# blue_pill.net
KiCad netlist of a schematic drawn in Altium Designer
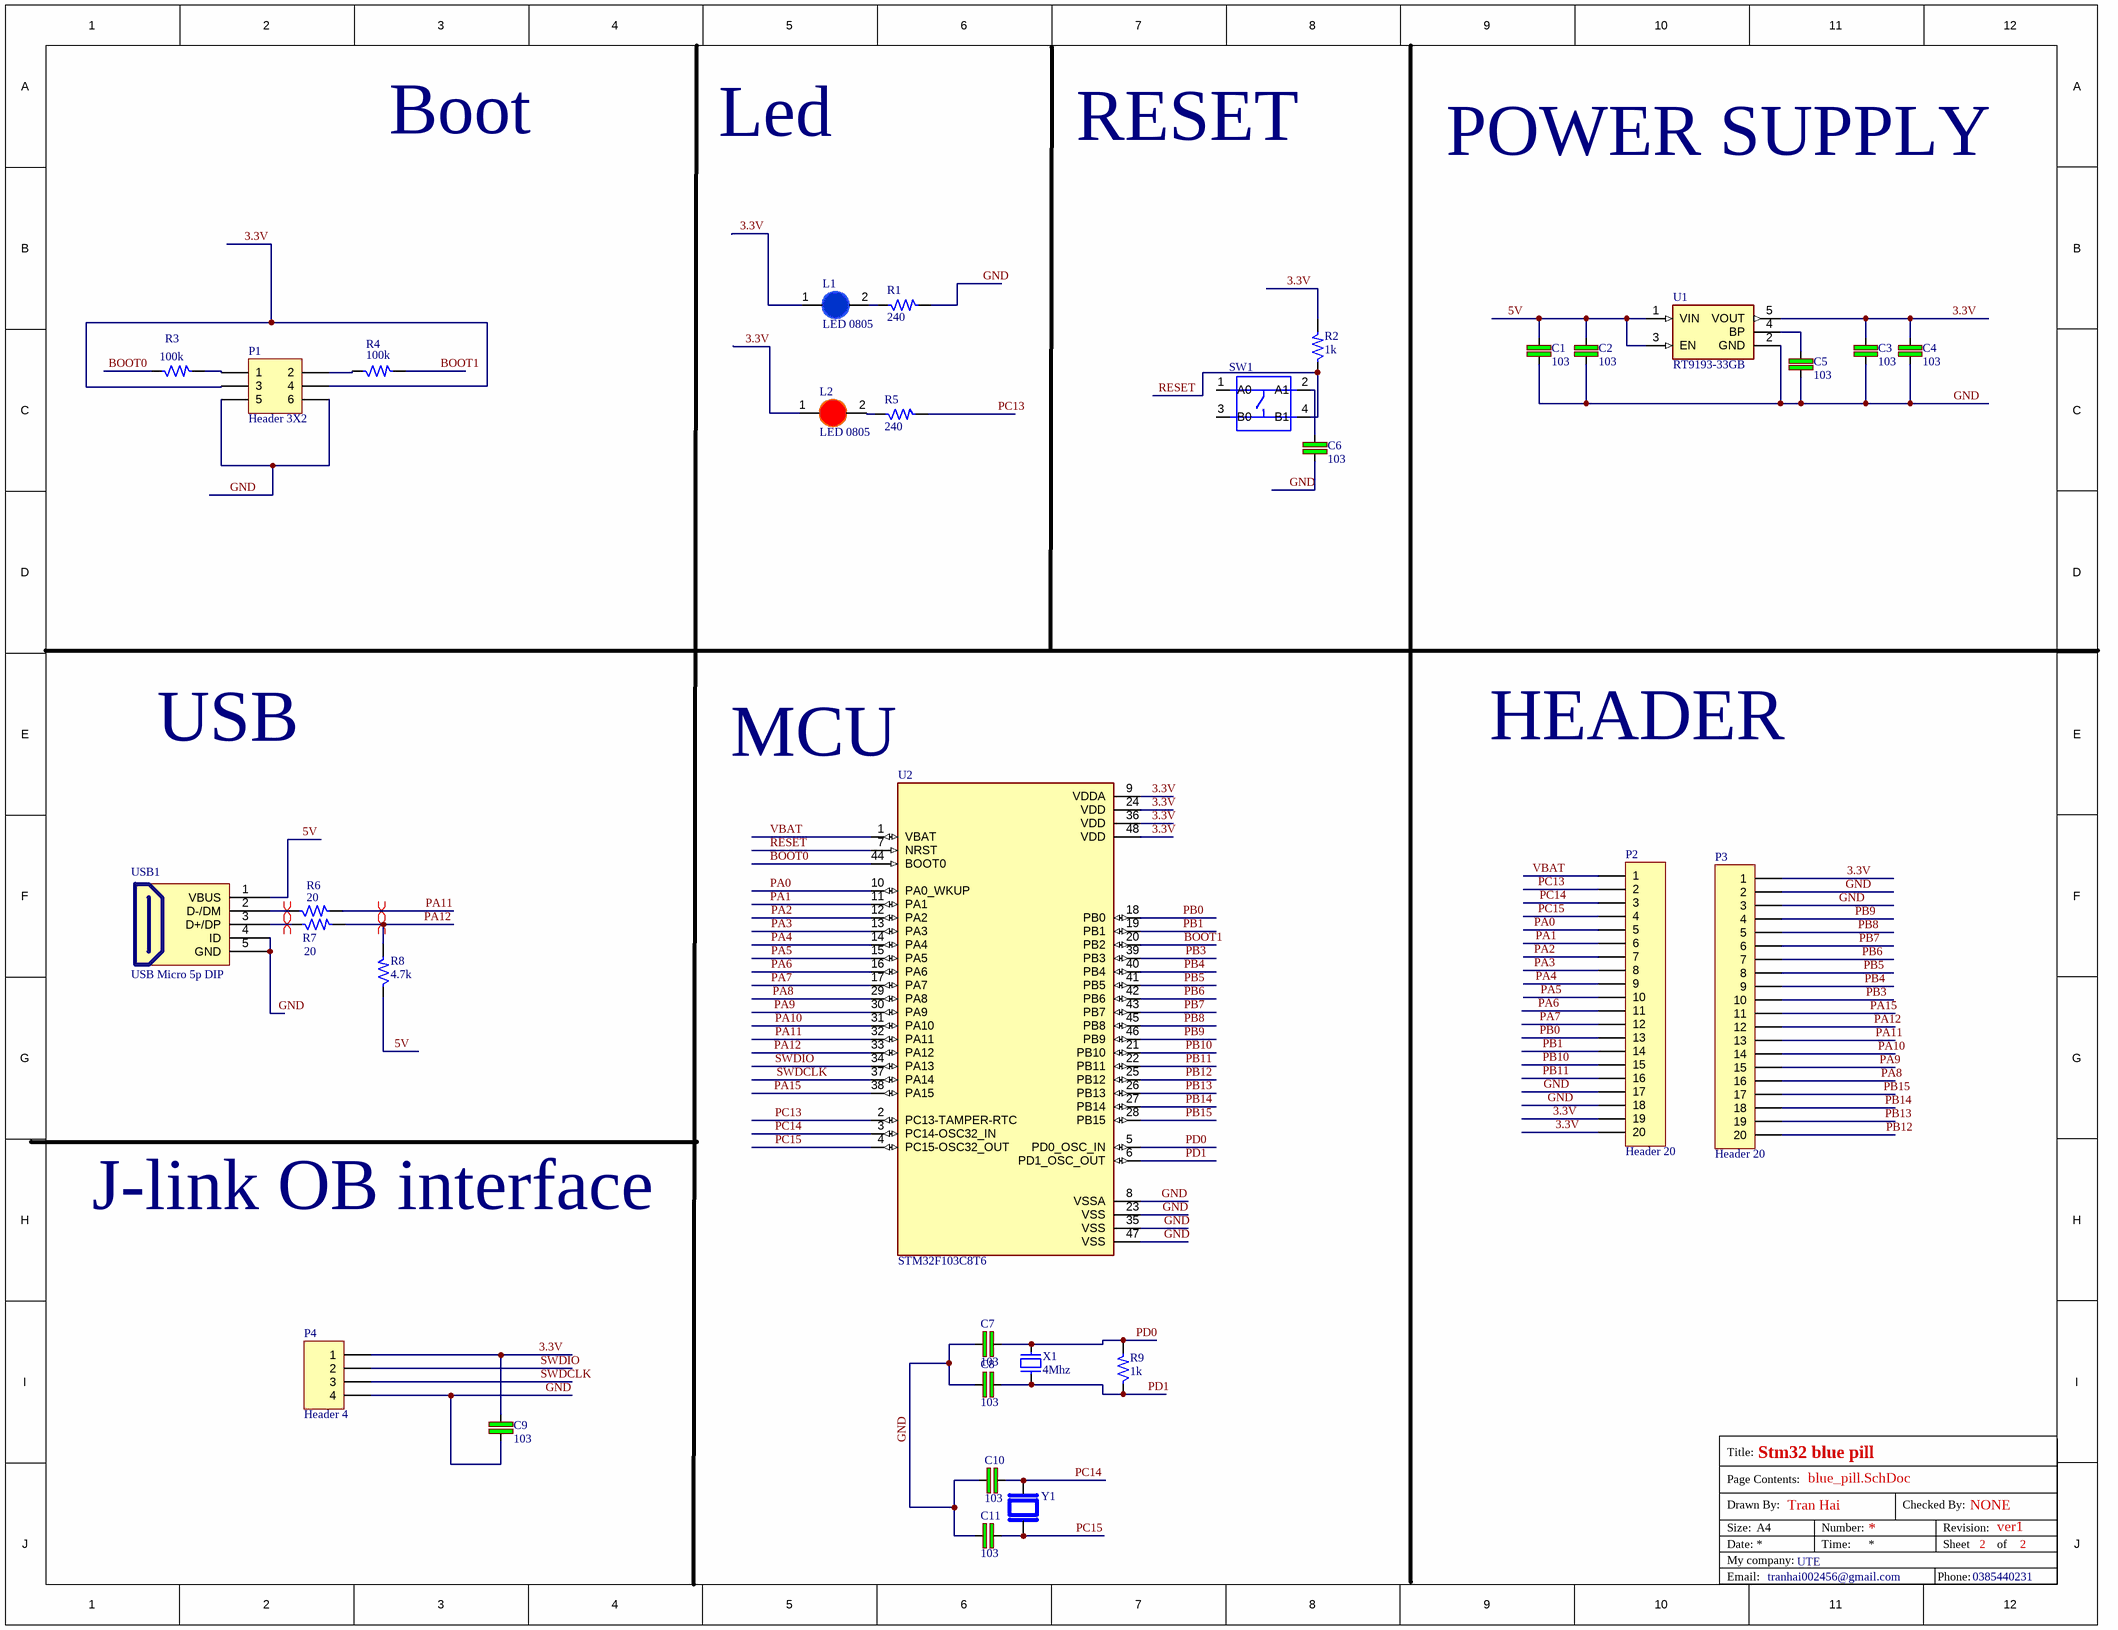
[diagram p0: blue_pill.SchDoc]

(export (version "E")
  (design (tool "Eeschema 10.0.6"))
  (components
    (comp (ref "C1")
      (value "103")
      (footprint "C-0805")
      (description "Cap SMD")
      (libsource (lib "") (part "C_1"))
    )
    (comp (ref "C2")
      (value "103")
      (footprint "C-0805")
      (description "Cap SMD")
      (libsource (lib "") (part "C_1"))
    )
    (comp (ref "C3")
      (value "103")
      (footprint "C-0805")
      (description "Cap SMD")
      (libsource (lib "") (part "C_1"))
    )
    (comp (ref "C4")
      (value "103")
      (footprint "C-0805")
      (description "Cap SMD")
      (libsource (lib "") (part "C_1"))
    )
    (comp (ref "C5")
      (value "103")
      (footprint "C-0805")
      (description "Cap SMD")
      (libsource (lib "") (part "C_1"))
    )
    (comp (ref "C6")
      (value "103")
      (footprint "C-0805")
      (description "Cap SMD")
      (libsource (lib "") (part "C_1"))
    )
    (comp (ref "C7")
      (value "103")
      (footprint "C-0805")
      (description "Cap SMD")
      (libsource (lib "Library AL") (part "C"))
    )
    (comp (ref "C8")
      (value "103")
      (footprint "C-0805")
      (description "Cap SMD")
      (libsource (lib "Library AL") (part "C"))
    )
    (comp (ref "C9")
      (value "103")
      (footprint "C-0805")
      (description "Cap SMD")
      (libsource (lib "") (part "C_1"))
    )
    (comp (ref "C10")
      (value "103")
      (footprint "C-0805")
      (description "Cap SMD")
      (libsource (lib "Library AL") (part "C"))
    )
    (comp (ref "C11")
      (value "103")
      (footprint "C-0805")
      (description "Cap SMD")
      (libsource (lib "Library AL") (part "C"))
    )
    (comp (ref "L1")
      (value "LED 0805")
      (footprint "LED-0805-Blue")
      (description "Dán")
      (libsource (lib "Altium_Lib_by_KhueNguyenCreator") (part "LED 0805 Xanh Duong"))
    )
    (comp (ref "L2")
      (value "LED 0805")
      (footprint "LED-0805-Red")
      (description "Dán")
      (libsource (lib "Altium_Lib_by_KhueNguyenCreator") (part "LED 0805 Do"))
    )
    (comp (ref "P1")
      (value "Header 3X2")
      (footprint "HDR2X3")
      (description "Header, 3-Pin, Dual row")
      (fields (field (name "PUBLISHER") "Altium Limited"))
      (libsource (lib "Library AL") (part "Header 3X2"))
    )
    (comp (ref "P2")
      (value "Header 20")
      (footprint "HDR1X20")
      (description "Header, 20-Pin")
      (fields (field (name "PUBLISHER") "Altium Limited"))
      (libsource (lib "Library AL") (part "Header 20"))
    )
    (comp (ref "P3")
      (value "Header 20")
      (footprint "HDR1X20")
      (description "Header, 20-Pin")
      (fields (field (name "PUBLISHER") "Altium Limited"))
      (libsource (lib "") (part "Header 20_1"))
    )
    (comp (ref "P4")
      (value "Header 4")
      (footprint "HDR1X4")
      (description "Header, 4-Pin")
      (fields (field (name "PUBLISHER") "Altium Limited"))
      (libsource (lib "Library AL") (part "Header 4"))
    )
    (comp (ref "R1")
      (value "240")
      (footprint "SM-1206")
      (description "Resistor 1/4W")
      (libsource (lib "Library AL") (part "R"))
    )
    (comp (ref "R2")
      (value "1k")
      (footprint "SM-1206")
      (description "Resistor 1/4W")
      (libsource (lib "Library AL") (part "R"))
    )
    (comp (ref "R3")
      (value "100k")
      (footprint "SM-1206")
      (description "Resistor 1/4W")
      (libsource (lib "Library AL") (part "R"))
    )
    (comp (ref "R4")
      (value "100k")
      (footprint "SM-1206")
      (description "Resistor 1/4W")
      (libsource (lib "Library AL") (part "R"))
    )
    (comp (ref "R5")
      (value "240")
      (footprint "SM-1206")
      (description "Resistor 1/4W")
      (libsource (lib "Library AL") (part "R"))
    )
    (comp (ref "R6")
      (value "20")
      (footprint "SM-1206")
      (description "Resistor 1/4W")
      (libsource (lib "Library AL") (part "R"))
    )
    (comp (ref "R7")
      (value "20")
      (footprint "SM-1206")
      (description "Resistor 1/4W")
      (libsource (lib "Library AL") (part "R"))
    )
    (comp (ref "R8")
      (value "4.7k")
      (footprint "SM-1206")
      (description "Resistor 1/4W")
      (libsource (lib "Library AL") (part "R"))
    )
    (comp (ref "R9")
      (value "1k")
      (footprint "SM-1206")
      (description "Resistor 1/4W")
      (libsource (lib "Library AL") (part "R"))
    )
    (comp (ref "SW1")
      (value "SMD-BUTTON(4P-5.2X5.2X1.5MM-SKQGAKE010)")
      (footprint "SW4-SMD-5.2X5.2X1.5MM")
      (description "Switch Tactile N.O. SPST Button Gull Wing 0.05A 12VDC 3.43N SMD T/R")
      (fields (field (name "MF") "ALPS") (field (name "MP") "SKQGAKE010"))
      (libsource (lib "SMD-BUTTON_4P-5.2X5.2X1.5MM-SKQGAKE010_") (part "SMD-BUTTON(4P-5.2X5.2X1.5MM-SKQGAKE010)"))
    )
    (comp (ref "U1")
      (value "RT9193-33GB")
      (footprint "SOT94P279X129-5N")
      (description "Linear Voltage Regulator IC Positive Fixed 1 Output 300mA TSOT-23-5")
      (fields (field (name "MF") "Richtek USA") (field (name "DIGI-KEY_PART_NUMBER") "1028-1014-2-ND"))
      (libsource (lib "RT9193-33GB") (part "RT9193-33GB"))
    )
    (comp (ref "U2")
      (value "STM32F103C8T6")
      (footprint "QFP50P900X900X160-48N")
      (description "ARM® Cortex®-M3 STM32F1 Microcontroller IC 32-Bit 72MHz 64KB (64K x 8) FLASH 48-LQFP (7x7)")
      (fields (field (name "MF") "STMicroelectronics"))
      (libsource (lib "STM32F103C8T6") (part "STM32F103C8T6"))
    )
    (comp (ref "USB1")
      (value "USB Micro 5p DIP")
      (footprint "USB Micro 5p DIP")
      (description "USB Type B")
      (libsource (lib "Altium_Lib_by_KhueNguyenCreator") (part "USB Micro 5p DIP"))
    )
    (comp (ref "X1")
      (value "4Mhz")
      (footprint "XT2")
      (description "Crystal For all Crystal 2pin.")
      (libsource (lib "syhaunguyen") (part "XT2"))
    )
    (comp (ref "Y1")
      (value "ABS07-32.768KHZ-T")
      (footprint "XTAL_ABS07-32.768KHZ-T")
      (description "32.768 kHz Â±20ppm Crystal 12.5pF 70 kOhms 2-SMD, No Lead")
      (fields (field (name "MF") "Abracon"))
      (libsource (lib "ABS07-32.768KHZ-T") (part "ABS07-32.768KHZ-T"))
    )
  )
  (nets
    (net (code "1") (name "/3.3V") (class "Default")
      (node (ref "C3") (pin "2") (pinfunction "2_2") (pintype "passive"))
      (node (ref "C4") (pin "2") (pinfunction "2_2") (pintype "passive"))
      (node (ref "C9") (pin "2") (pinfunction "2_2") (pintype "passive"))
      (node (ref "L1") (pin "1") (pinfunction "A_1") (pintype "passive"))
      (node (ref "L2") (pin "1") (pinfunction "A_1") (pintype "passive"))
      (node (ref "P1") (pin "3") (pinfunction "3_3") (pintype "passive"))
      (node (ref "P1") (pin "4") (pinfunction "4_4") (pintype "passive"))
      (node (ref "P2") (pin "19") (pinfunction "19_19") (pintype "passive"))
      (node (ref "P2") (pin "20") (pinfunction "20_20") (pintype "passive"))
      (node (ref "P3") (pin "1") (pinfunction "1_1") (pintype "passive"))
      (node (ref "P4") (pin "1") (pinfunction "1_1") (pintype "passive"))
      (node (ref "R2") (pin "2") (pinfunction "2_2") (pintype "passive"))
      (node (ref "U1") (pin "5") (pinfunction "VOUT_5") (pintype "output"))
      (node (ref "U2") (pin "24") (pinfunction "VDD_24") (pintype "power_in"))
      (node (ref "U2") (pin "36") (pinfunction "VDD_36") (pintype "power_in"))
      (node (ref "U2") (pin "48") (pinfunction "VDD_48") (pintype "power_in"))
      (node (ref "U2") (pin "9") (pinfunction "VDDA_9") (pintype "power_in"))
    )
    (net (code "2") (name "/5V") (class "Default")
      (node (ref "C1") (pin "2") (pinfunction "2_2") (pintype "passive"))
      (node (ref "C2") (pin "2") (pinfunction "2_2") (pintype "passive"))
      (node (ref "R8") (pin "1") (pinfunction "1_1") (pintype "passive"))
      (node (ref "U1") (pin "1") (pinfunction "VIN_1") (pintype "input"))
      (node (ref "U1") (pin "3") (pinfunction "EN_3") (pintype "input"))
      (node (ref "USB1") (pin "1") (pinfunction "VBUS_1") (pintype "passive"))
    )
    (net (code "3") (name "/BOOT0") (class "Default")
      (node (ref "R3") (pin "1") (pinfunction "1_1") (pintype "passive"))
      (node (ref "U2") (pin "44") (pinfunction "BOOT0_44") (pintype "input"))
    )
    (net (code "4") (name "/BOOT1") (class "Default")
      (node (ref "R4") (pin "2") (pinfunction "2_2") (pintype "passive"))
      (node (ref "U2") (pin "20") (pinfunction "PB2_20") (pintype "bidirectional"))
    )
    (net (code "5") (name "/GND") (class "Default")
      (node (ref "C1") (pin "1") (pinfunction "1_1") (pintype "passive"))
      (node (ref "C10") (pin "1") (pinfunction "1_1") (pintype "passive"))
      (node (ref "C11") (pin "1") (pinfunction "1_1") (pintype "passive"))
      (node (ref "C2") (pin "1") (pinfunction "1_1") (pintype "passive"))
      (node (ref "C3") (pin "1") (pinfunction "1_1") (pintype "passive"))
      (node (ref "C4") (pin "1") (pinfunction "1_1") (pintype "passive"))
      (node (ref "C5") (pin "1") (pinfunction "1_1") (pintype "passive"))
      (node (ref "C6") (pin "1") (pinfunction "1_1") (pintype "passive"))
      (node (ref "C7") (pin "1") (pinfunction "1_1") (pintype "passive"))
      (node (ref "C8") (pin "1") (pinfunction "1_1") (pintype "passive"))
      (node (ref "C9") (pin "1") (pinfunction "1_1") (pintype "passive"))
      (node (ref "P1") (pin "5") (pinfunction "5_5") (pintype "passive"))
      (node (ref "P1") (pin "6") (pinfunction "6_6") (pintype "passive"))
      (node (ref "P2") (pin "17") (pinfunction "17_17") (pintype "passive"))
      (node (ref "P2") (pin "18") (pinfunction "18_18") (pintype "passive"))
      (node (ref "P3") (pin "2") (pinfunction "2_2") (pintype "passive"))
      (node (ref "P3") (pin "3") (pinfunction "3_3") (pintype "passive"))
      (node (ref "P4") (pin "4") (pinfunction "4_4") (pintype "passive"))
      (node (ref "R1") (pin "2") (pinfunction "2_2") (pintype "passive"))
      (node (ref "U1") (pin "2") (pinfunction "GND_2") (pintype "power_in"))
      (node (ref "U2") (pin "23") (pinfunction "VSS_23") (pintype "power_in"))
      (node (ref "U2") (pin "35") (pinfunction "VSS_35") (pintype "power_in"))
      (node (ref "U2") (pin "47") (pinfunction "VSS_47") (pintype "power_in"))
      (node (ref "U2") (pin "8") (pinfunction "VSSA_8") (pintype "power_in"))
      (node (ref "USB1") (pin "4") (pinfunction "ID_4") (pintype "passive"))
      (node (ref "USB1") (pin "5") (pinfunction "GND_5") (pintype "passive"))
    )
    (net (code "6") (name "/PA0") (class "Default")
      (node (ref "P2") (pin "5") (pinfunction "5_5") (pintype "passive"))
      (node (ref "U2") (pin "10") (pinfunction "PA0_WKUP_10") (pintype "bidirectional"))
    )
    (net (code "7") (name "/PA1") (class "Default")
      (node (ref "P2") (pin "6") (pinfunction "6_6") (pintype "passive"))
      (node (ref "U2") (pin "11") (pinfunction "PA1_11") (pintype "bidirectional"))
    )
    (net (code "8") (name "/PA2") (class "Default")
      (node (ref "P2") (pin "7") (pinfunction "7_7") (pintype "passive"))
      (node (ref "U2") (pin "12") (pinfunction "PA2_12") (pintype "bidirectional"))
    )
    (net (code "9") (name "/PA3") (class "Default")
      (node (ref "P2") (pin "8") (pinfunction "8_8") (pintype "passive"))
      (node (ref "U2") (pin "13") (pinfunction "PA3_13") (pintype "bidirectional"))
    )
    (net (code "10") (name "/PA4") (class "Default")
      (node (ref "P2") (pin "9") (pinfunction "9_9") (pintype "passive"))
      (node (ref "U2") (pin "14") (pinfunction "PA4_14") (pintype "bidirectional"))
    )
    (net (code "11") (name "/PA5") (class "Default")
      (node (ref "P2") (pin "10") (pinfunction "10_10") (pintype "passive"))
      (node (ref "U2") (pin "15") (pinfunction "PA5_15") (pintype "bidirectional"))
    )
    (net (code "12") (name "/PA6") (class "Default")
      (node (ref "P2") (pin "11") (pinfunction "11_11") (pintype "passive"))
      (node (ref "U2") (pin "16") (pinfunction "PA6_16") (pintype "bidirectional"))
    )
    (net (code "13") (name "/PA7") (class "Default")
      (node (ref "P2") (pin "12") (pinfunction "12_12") (pintype "passive"))
      (node (ref "U2") (pin "17") (pinfunction "PA7_17") (pintype "bidirectional"))
    )
    (net (code "14") (name "/PA8") (class "Default")
      (node (ref "P3") (pin "16") (pinfunction "16_16") (pintype "passive"))
      (node (ref "U2") (pin "29") (pinfunction "PA8_29") (pintype "bidirectional"))
    )
    (net (code "15") (name "/PA9") (class "Default")
      (node (ref "P3") (pin "15") (pinfunction "15_15") (pintype "passive"))
      (node (ref "U2") (pin "30") (pinfunction "PA9_30") (pintype "bidirectional"))
    )
    (net (code "16") (name "/PA10") (class "Default")
      (node (ref "P3") (pin "14") (pinfunction "14_14") (pintype "passive"))
      (node (ref "U2") (pin "31") (pinfunction "PA10_31") (pintype "bidirectional"))
    )
    (net (code "17") (name "/PA11") (class "Default")
      (node (ref "P3") (pin "13") (pinfunction "13_13") (pintype "passive"))
      (node (ref "R6") (pin "2") (pinfunction "2_2") (pintype "passive"))
      (node (ref "U2") (pin "32") (pinfunction "PA11_32") (pintype "bidirectional"))
    )
    (net (code "18") (name "/PA12") (class "Default")
      (node (ref "P3") (pin "12") (pinfunction "12_12") (pintype "passive"))
      (node (ref "R7") (pin "2") (pinfunction "2_2") (pintype "passive"))
      (node (ref "R8") (pin "2") (pinfunction "2_2") (pintype "passive"))
      (node (ref "U2") (pin "33") (pinfunction "PA12_33") (pintype "bidirectional"))
    )
    (net (code "19") (name "/PA15") (class "Default")
      (node (ref "P3") (pin "11") (pinfunction "11_11") (pintype "passive"))
      (node (ref "U2") (pin "38") (pinfunction "PA15_38") (pintype "bidirectional"))
    )
    (net (code "20") (name "/PB0") (class "Default")
      (node (ref "P2") (pin "13") (pinfunction "13_13") (pintype "passive"))
      (node (ref "U2") (pin "18") (pinfunction "PB0_18") (pintype "bidirectional"))
    )
    (net (code "21") (name "/PB1") (class "Default")
      (node (ref "P2") (pin "14") (pinfunction "14_14") (pintype "passive"))
      (node (ref "U2") (pin "19") (pinfunction "PB1_19") (pintype "bidirectional"))
    )
    (net (code "22") (name "/PB3") (class "Default")
      (node (ref "P3") (pin "10") (pinfunction "10_10") (pintype "passive"))
      (node (ref "U2") (pin "39") (pinfunction "PB3_39") (pintype "bidirectional"))
    )
    (net (code "23") (name "/PB4") (class "Default")
      (node (ref "P3") (pin "9") (pinfunction "9_9") (pintype "passive"))
      (node (ref "U2") (pin "40") (pinfunction "PB4_40") (pintype "bidirectional"))
    )
    (net (code "24") (name "/PB5") (class "Default")
      (node (ref "P3") (pin "8") (pinfunction "8_8") (pintype "passive"))
      (node (ref "U2") (pin "41") (pinfunction "PB5_41") (pintype "bidirectional"))
    )
    (net (code "25") (name "/PB6") (class "Default")
      (node (ref "P3") (pin "7") (pinfunction "7_7") (pintype "passive"))
      (node (ref "U2") (pin "42") (pinfunction "PB6_42") (pintype "bidirectional"))
    )
    (net (code "26") (name "/PB7") (class "Default")
      (node (ref "P3") (pin "6") (pinfunction "6_6") (pintype "passive"))
      (node (ref "U2") (pin "43") (pinfunction "PB7_43") (pintype "bidirectional"))
    )
    (net (code "27") (name "/PB8") (class "Default")
      (node (ref "P3") (pin "5") (pinfunction "5_5") (pintype "passive"))
      (node (ref "U2") (pin "45") (pinfunction "PB8_45") (pintype "bidirectional"))
    )
    (net (code "28") (name "/PB9") (class "Default")
      (node (ref "P3") (pin "4") (pinfunction "4_4") (pintype "passive"))
      (node (ref "U2") (pin "46") (pinfunction "PB9_46") (pintype "bidirectional"))
    )
    (net (code "29") (name "/PB10") (class "Default")
      (node (ref "P2") (pin "15") (pinfunction "15_15") (pintype "passive"))
      (node (ref "U2") (pin "21") (pinfunction "PB10_21") (pintype "bidirectional"))
    )
    (net (code "30") (name "/PB11") (class "Default")
      (node (ref "P2") (pin "16") (pinfunction "16_16") (pintype "passive"))
      (node (ref "U2") (pin "22") (pinfunction "PB11_22") (pintype "bidirectional"))
    )
    (net (code "31") (name "/PB12") (class "Default")
      (node (ref "P3") (pin "20") (pinfunction "20_20") (pintype "passive"))
      (node (ref "U2") (pin "25") (pinfunction "PB12_25") (pintype "bidirectional"))
    )
    (net (code "32") (name "/PB13") (class "Default")
      (node (ref "P3") (pin "19") (pinfunction "19_19") (pintype "passive"))
      (node (ref "U2") (pin "26") (pinfunction "PB13_26") (pintype "bidirectional"))
    )
    (net (code "33") (name "/PB14") (class "Default")
      (node (ref "P3") (pin "18") (pinfunction "18_18") (pintype "passive"))
      (node (ref "U2") (pin "27") (pinfunction "PB14_27") (pintype "bidirectional"))
    )
    (net (code "34") (name "/PB15") (class "Default")
      (node (ref "P3") (pin "17") (pinfunction "17_17") (pintype "passive"))
      (node (ref "U2") (pin "28") (pinfunction "PB15_28") (pintype "bidirectional"))
    )
    (net (code "35") (name "/PC13") (class "Default")
      (node (ref "P2") (pin "2") (pinfunction "2_2") (pintype "passive"))
      (node (ref "R5") (pin "2") (pinfunction "2_2") (pintype "passive"))
      (node (ref "U2") (pin "2") (pinfunction "PC13-TAMPER-RTC_2") (pintype "bidirectional"))
    )
    (net (code "36") (name "/PC14") (class "Default")
      (node (ref "C10") (pin "2") (pinfunction "2_2") (pintype "passive"))
      (node (ref "P2") (pin "3") (pinfunction "3_3") (pintype "passive"))
      (node (ref "U2") (pin "3") (pinfunction "PC14-OSC32_IN_3") (pintype "bidirectional"))
      (node (ref "Y1") (pin "2") (pinfunction "2_2") (pintype "passive"))
    )
    (net (code "37") (name "/PC15") (class "Default")
      (node (ref "C11") (pin "2") (pinfunction "2_2") (pintype "passive"))
      (node (ref "P2") (pin "4") (pinfunction "4_4") (pintype "passive"))
      (node (ref "U2") (pin "4") (pinfunction "PC15-OSC32_OUT_4") (pintype "bidirectional"))
      (node (ref "Y1") (pin "1") (pinfunction "1_1") (pintype "passive"))
    )
    (net (code "38") (name "/PD0") (class "Default")
      (node (ref "C7") (pin "2") (pinfunction "2_2") (pintype "passive"))
      (node (ref "R9") (pin "2") (pinfunction "2_2") (pintype "passive"))
      (node (ref "U2") (pin "5") (pinfunction "PD0_OSC_IN_5") (pintype "bidirectional"))
      (node (ref "X1") (pin "1") (pinfunction "1_1") (pintype "passive"))
    )
    (net (code "39") (name "/PD1") (class "Default")
      (node (ref "C8") (pin "2") (pinfunction "2_2") (pintype "passive"))
      (node (ref "R9") (pin "1") (pinfunction "1_1") (pintype "passive"))
      (node (ref "U2") (pin "6") (pinfunction "PD1_OSC_OUT_6") (pintype "bidirectional"))
      (node (ref "X1") (pin "2") (pinfunction "2_2") (pintype "passive"))
    )
    (net (code "40") (name "/RESET") (class "Default")
      (node (ref "R2") (pin "1") (pinfunction "1_1") (pintype "passive"))
      (node (ref "SW1") (pin "4") (pinfunction "B1_4") (pintype "bidirectional"))
      (node (ref "U2") (pin "7") (pinfunction "NRST_7") (pintype "input"))
    )
    (net (code "41") (name "/SWDCLK") (class "Default")
      (node (ref "P4") (pin "3") (pinfunction "3_3") (pintype "passive"))
      (node (ref "U2") (pin "37") (pinfunction "PA14_37") (pintype "bidirectional"))
    )
    (net (code "42") (name "/SWDIO") (class "Default")
      (node (ref "P4") (pin "2") (pinfunction "2_2") (pintype "passive"))
      (node (ref "U2") (pin "34") (pinfunction "PA13_34") (pintype "bidirectional"))
    )
    (net (code "43") (name "/VBAT") (class "Default")
      (node (ref "P2") (pin "1") (pinfunction "1_1") (pintype "passive"))
      (node (ref "U2") (pin "1") (pinfunction "VBAT_1") (pintype "bidirectional"))
    )
    (net (code "44") (name "Net-(L1-K)") (class "Default")
      (node (ref "L1") (pin "2") (pinfunction "K_2") (pintype "passive"))
      (node (ref "R1") (pin "1") (pinfunction "1_1") (pintype "passive"))
    )
    (net (code "45") (name "Net-(L2-K)") (class "Default")
      (node (ref "L2") (pin "2") (pinfunction "K_2") (pintype "passive"))
      (node (ref "R5") (pin "1") (pinfunction "1_1") (pintype "passive"))
    )
    (net (code "46") (name "Net-(P1-Pad1)") (class "Default")
      (node (ref "P1") (pin "1") (pinfunction "1_1") (pintype "passive"))
      (node (ref "R3") (pin "2") (pinfunction "2_2") (pintype "passive"))
    )
    (net (code "47") (name "Net-(P1-Pad2)") (class "Default")
      (node (ref "P1") (pin "2") (pinfunction "2_2") (pintype "passive"))
      (node (ref "R4") (pin "1") (pinfunction "1_1") (pintype "passive"))
    )
    (net (code "48") (name "Net-(SW1-A1)") (class "Default")
      (node (ref "C6") (pin "2") (pinfunction "2_2") (pintype "passive"))
      (node (ref "SW1") (pin "2") (pinfunction "A1_2") (pintype "bidirectional"))
    )
    (net (code "49") (name "Net-(U1-BP)") (class "Default")
      (node (ref "C5") (pin "2") (pinfunction "2_2") (pintype "passive"))
      (node (ref "U1") (pin "4") (pinfunction "BP_4") (pintype "passive"))
    )
    (net (code "50") (name "Net-(USB1-D+{slash}DP)") (class "Default")
      (node (ref "R7") (pin "1") (pinfunction "1_1") (pintype "passive"))
      (node (ref "USB1") (pin "3") (pinfunction "D+/DP_3") (pintype "passive"))
    )
    (net (code "51") (name "Net-(USB1-D-{slash}DM)") (class "Default")
      (node (ref "R6") (pin "1") (pinfunction "1_1") (pintype "passive"))
      (node (ref "USB1") (pin "2") (pinfunction "D-/DM_2") (pintype "passive"))
    )
    (net (code "52") (name "unconnected-(SW1-A0-Pad1)") (class "Default")
      (node (ref "SW1") (pin "1") (pinfunction "A0_1") (pintype "bidirectional"))
    )
    (net (code "53") (name "unconnected-(SW1-B0-Pad3)") (class "Default")
      (node (ref "SW1") (pin "3") (pinfunction "B0_3") (pintype "bidirectional"))
    )
  )
)
